# 5_dc_dc_3V3_EPS_Beacon.net
KiCad netlist of a schematic drawn in Altium Designer
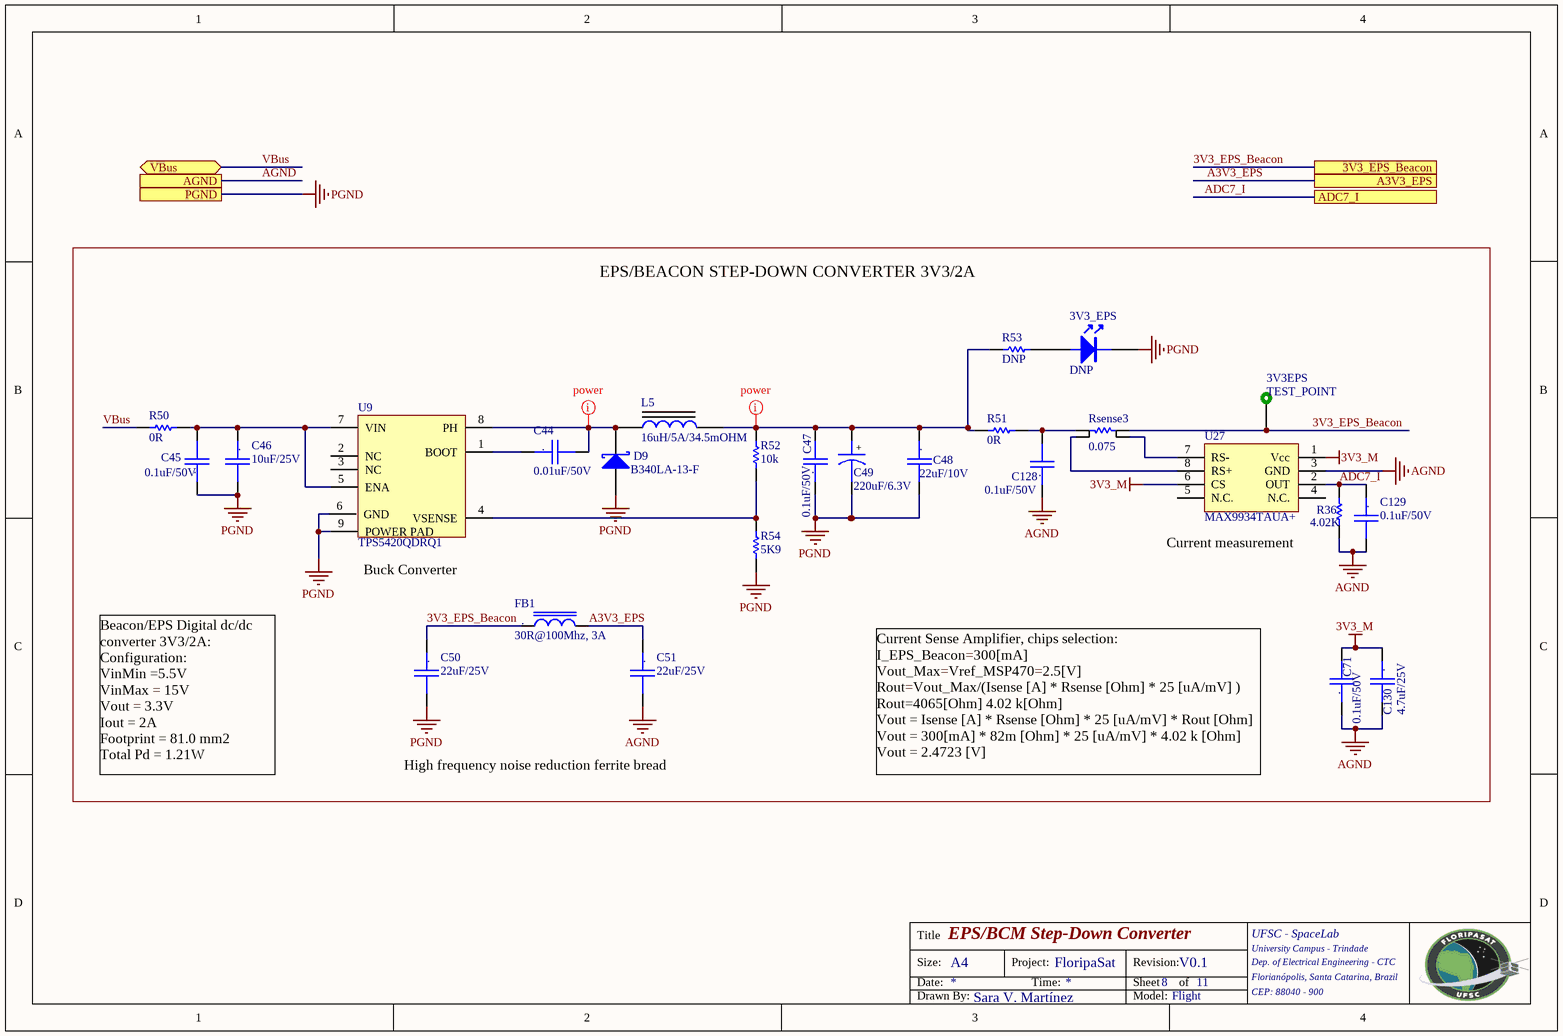
[diagram p0: 5_dc_dc_3V3_EPS_Beacon.SchDoc]

(export (version "E")
  (design (tool "Eeschema 10.0.6"))
  (components
    (comp (ref "3V3EPS")
      (value "TEST_POINT")
      (footprint "TEST_POINT")
      (description "Test point")
      (libsource (lib "Floripasat_lib") (part "TEST_POINT"))
    )
    (comp (ref "3V3_EPS")
      (value "DNP")
      (footprint "0603-LED")
      (description "SMD Green LED")
      (fields (field (name "PARTNUMBER") "150060VS75000"))
      (libsource (lib "FloripaSatSchlib") (part "LED/G_0603"))
    )
    (comp (ref "C44")
      (value "0.01uF/50V")
      (footprint "CC0805")
      (description "CAP CER 0.01uF 50V 10% X7R 0805")
      (fields (field (name "PARTNUMBER") "GRM216R71H103KA01D"))
      (libsource (lib "Floripasat_lib") (part "Cap_Cer_X7R_0.01uF_50V_0805"))
    )
    (comp (ref "C45")
      (value "0.1uF/50V")
      (footprint "CC0805")
      (description "CAP CER 0.1UF 50V 10% X7R 0805")
      (fields (field (name "PARTNUMBER") "GRM216R71H103KA01D"))
      (libsource (lib "FloripaSatSchlib") (part "Cap_Cer_X7R_0.1uF_25V_0805"))
    )
    (comp (ref "C46")
      (value "10uF/25V")
      (footprint "CC1206")
      (description "CAP CER 10uF 25V 10% X7R 1206")
      (fields (field (name "PARTNUMBER") "GRM31CR71E106KA12L"))
      (libsource (lib "Floripasat_lib") (part "Cap_Cer_X7R_10uF_25V_1206"))
    )
    (comp (ref "C47")
      (value "0.1uF/50V")
      (footprint "CC0805")
      (description "CAP CER 0.1UF 50V 10% X7R 0805")
      (fields (field (name "PARTNUMBER") "GRM216R71H103KA01D"))
      (libsource (lib "FloripaSatSchlib") (part "Cap_Cer_X7R_0.1uF_25V_0805"))
    )
    (comp (ref "C48")
      (value "22uF/10V")
      (footprint "CC1206")
      (description "CAP CER 22uF 10V 10% X7R 1206")
      (fields (field (name "PARTNUMBER") "GRM31CR71A226KE15L"))
      (libsource (lib "FloripaSatSchlib") (part "Cap_Cer_X7R_22uF_10V_1206"))
    )
    (comp (ref "C49")
      (value "220uF/6.3V")
      (footprint "FloripaSatPcbLib:cc1210")
      (description "CAP Tantalum 220uF 6.3V 20% 1210")
      (fields (field (name "PARTNUMBER") "6TPE220MAZB"))
      (libsource (lib "Floripasat_lib") (part "Cap_Tant_SMD_220uF_6.3V_1210"))
    )
    (comp (ref "C50")
      (value "22uF/25V")
      (footprint "CC1210")
      (description "CAP CER 22uF 25V 10% X7R 1210")
      (fields (field (name "PARTNUMBER") "GRM32ER71E226KE15L"))
      (libsource (lib "FloripaSatSchlib") (part "Cap_Cer_X7R_0.01uF_16V_1210"))
    )
    (comp (ref "C51")
      (value "22uF/25V")
      (footprint "CC1210")
      (description "CAP CER 22uF 25V 10% X7R 1210")
      (fields (field (name "PARTNUMBER") "GRM32ER71E226KE15L"))
      (libsource (lib "FloripaSatSchlib") (part "Cap_Cer_X7R_0.01uF_16V_1210"))
    )
    (comp (ref "C71")
      (value "0.1uF/50V")
      (footprint "CC0603")
      (description "CAP CER 0.1UF 50V 10% X7R 0603")
      (fields (field (name "PARTNUMBER") "GRM188R71H104KA93D"))
      (libsource (lib "FloripaSatSchlib") (part "Cap_Cer_X7R_0.1uF_50V_0603"))
    )
    (comp (ref "C128")
      (value "0.1uF/50V")
      (footprint "CC0603")
      (description "CAP CER 0.1UF 50V 10% X7R 0603")
      (fields (field (name "PARTNUMBER") "GRM188R71H104KA93D"))
      (libsource (lib "FloripaSatSchlib") (part "Cap_Cer_X7R_0.1uF_50V_0603"))
    )
    (comp (ref "C129")
      (value "0.1uF/50V")
      (footprint "CC0603")
      (description "CAP CER 0.1UF 50V 10% X7R 0603")
      (fields (field (name "PARTNUMBER") "GRM188R71H104KA93D"))
      (libsource (lib "FloripaSatSchlib") (part "Cap_Cer_X7R_0.1uF_50V_0603"))
    )
    (comp (ref "C130")
      (value "4.7uF/25V")
      (footprint "CC0805")
      (description "CAP CER 4.7uF 25V 10% X7R 0805")
      (fields (field (name "PARTNUMBER") "GRM21BR71E475KA73L"))
      (libsource (lib "FloripaSatSchlib") (part "Cap_Cer_X7R_4.7uF_25V_0805"))
    )
    (comp (ref "D9")
      (value "B340LA-13-F")
      (footprint "DO-214AC")
      (description "DIODE SCHOTTKY 40V 3A B340LA-13-F")
      (libsource (lib "FloripaSatSchlib") (part "DIODE_SCHOTTKY_40V_3A_B340LA-13-F"))
    )
    (comp (ref "FB1")
      (value "30R@100Mhz, 3A")
      (footprint "IND0805")
      (description "Ferrite Bead 30 OHM 3A 100MHz")
      (fields (field (name "PARTNUMBER") "BLM21PG300SN1D"))
      (libsource (lib "FloripaSatSchlib") (part "FB_30R_3A_100MHz_0805"))
    )
    (comp (ref "L5")
      (value "16uH/5A/34.5mOHM")
      (footprint "IND_744325xxx")
      (description "INDUCTOR 16UH 5A SMD")
      (fields (field (name "PARTNUMBER") "7443251600"))
      (libsource (lib "FloripaSatSchlib") (part "IND_POWER_16uH_5A_35.5mR"))
    )
    (comp (ref "R36")
      (value "4.02K")
      (footprint "0805")
      (description "RES 3k3 OHM 1/10W 0.1% 0805")
      (fields (field (name "PARTNUMBER") "CPF0805B3K3E1"))
      (libsource (lib "FloripaSatSchlib") (part "R3.3k_0.1%_1/10W_0805"))
    )
    (comp (ref "R50")
      (value "0R")
      (footprint "1206")
      (description "RES 0.0 OHM 1/2W JUMP 1206")
      (fields (field (name "PARTNUMBER") "CRCW12060000Z0EAHP"))
      (libsource (lib "FloripaSatSchlib") (part "R0R_JUMPER_1/2W_1206"))
    )
    (comp (ref "R51")
      (value "0R")
      (footprint "1206")
      (description "RES 0.0 OHM 1/2W JUMP 1206")
      (fields (field (name "PARTNUMBER") "CRCW12060000Z0EAHP"))
      (libsource (lib "FloripaSatSchlib") (part "R0R_JUMPER_1/2W_1206"))
    )
    (comp (ref "R52")
      (value "10k")
      (footprint "0805")
      (description "RES 10K OHM 1/8W 1%  0805")
      (fields (field (name "PARTNUMBER") "CRCW080510K0FKEA"))
      (libsource (lib "FloripaSatSchlib") (part "R10k_1%_1/8W_0805"))
    )
    (comp (ref "R53")
      (value "DNP")
      (footprint "0603")
      (description "RES 1.0K OHM 1/8W 1% 0603")
      (fields (field (name "PARTNUMBER") "MCT06030C1001FP500"))
      (libsource (lib "FloripaSatSchlib") (part "R1.0k_1%_1/8W_0603"))
    )
    (comp (ref "R54")
      (value "5K9")
      (footprint "0805")
      (description "RES 5K9 OHM 1/8W 1% 0805")
      (fields (field (name "PARTNUMBER") "71-CRCW0805-5.9K-E3"))
      (libsource (lib "FloripaSatSchlib") (part "R5.9K_1%_1/8W_0805"))
    )
    (comp (ref "Rsense3")
      (value "0.075")
      (footprint "1206 - ohmite")
      (description "Current Sense Resistors - SMD 0.05ohm .5% 4 Terminal")
      (fields (field (name "PARTNUMBER") "LVK12R050DER"))
      (libsource (lib "FloripaSatSchlib") (part "R0.05R_0.5%_0.5W_1206"))
    )
    (comp (ref "U9")
      (value "TPS5420QDRQ1")
      (footprint "SO8 Power PAD")
      (libsource (lib "FloripaSatSchlib") (part "TPS5420QDRQ1"))
    )
    (comp (ref "U27")
      (value "MAX9934TAUA+")
      (footprint "MSOP-8")
      (libsource (lib "componentes_6_11") (part "MAX9934TAUA+"))
    )
  )
  (nets
    (net (code "1") (name "/3V3_EPS_Beacon") (class "Default")
      (node (ref "3V3EPS") (pin "1") (pinfunction "1_1") (pintype "passive"))
      (node (ref "C50") (pin "1") (pinfunction "1_1") (pintype "passive"))
      (node (ref "FB1") (pin "1") (pinfunction "1_1") (pintype "passive"))
      (node (ref "Rsense3") (pin "2") (pinfunction "2_2") (pintype "passive"))
    )
    (net (code "2") (name "/A3V3_EPS") (class "Default")
      (node (ref "C51") (pin "1") (pinfunction "1_1") (pintype "passive"))
      (node (ref "FB1") (pin "2") (pinfunction "2_2") (pintype "passive"))
    )
    (net (code "3") (name "/ADC7_I") (class "Default")
      (node (ref "C129") (pin "1") (pinfunction "1_1") (pintype "passive"))
      (node (ref "R36") (pin "2") (pinfunction "2_2") (pintype "passive"))
      (node (ref "U27") (pin "2") (pinfunction "OUT_2") (pintype "passive"))
    )
    (net (code "4") (name "/VBus") (class "Default")
      (node (ref "R50") (pin "2") (pinfunction "2_2") (pintype "passive"))
    )
    (net (code "5") (name "3V3_M") (class "Default")
      (node (ref "C130") (pin "1") (pinfunction "1_1") (pintype "passive"))
      (node (ref "C71") (pin "2") (pinfunction "2_2") (pintype "passive"))
      (node (ref "U27") (pin "1") (pinfunction "Vcc_1") (pintype "passive"))
      (node (ref "U27") (pin "6") (pinfunction "CS_6") (pintype "passive"))
    )
    (net (code "6") (name "AGND") (class "Default")
      (node (ref "C128") (pin "1") (pinfunction "1_1") (pintype "passive"))
      (node (ref "C129") (pin "2") (pinfunction "2_2") (pintype "passive"))
      (node (ref "C130") (pin "2") (pinfunction "2_2") (pintype "passive"))
      (node (ref "C51") (pin "2") (pinfunction "2_2") (pintype "passive"))
      (node (ref "C71") (pin "1") (pinfunction "1_1") (pintype "passive"))
      (node (ref "R36") (pin "1") (pinfunction "1_1") (pintype "passive"))
      (node (ref "U27") (pin "3") (pinfunction "GND_3") (pintype "passive"))
    )
    (net (code "7") (name "Net-(3V3_EPS-A)") (class "Default")
      (node (ref "3V3_EPS") (pin "1") (pinfunction "A_1") (pintype "passive"))
      (node (ref "R53") (pin "1") (pinfunction "1_1") (pintype "passive"))
    )
    (net (code "8") (name "Net-(C47-Pad2)") (class "Default")
      (node (ref "C47") (pin "2") (pinfunction "2_2") (pintype "passive"))
      (node (ref "C48") (pin "1") (pinfunction "1_1") (pintype "passive"))
      (node (ref "C49") (pin "1") (pinfunction "1_1") (pintype "passive"))
      (node (ref "L5") (pin "2") (pinfunction "2_2") (pintype "passive"))
      (node (ref "R51") (pin "2") (pinfunction "2_2") (pintype "passive"))
      (node (ref "R52") (pin "2") (pinfunction "2_2") (pintype "passive"))
      (node (ref "R53") (pin "2") (pinfunction "2_2") (pintype "passive"))
    )
    (net (code "9") (name "Net-(C128-Pad2)") (class "Default")
      (node (ref "C128") (pin "2") (pinfunction "2_2") (pintype "passive"))
      (node (ref "R51") (pin "1") (pinfunction "1_1") (pintype "passive"))
      (node (ref "Rsense3") (pin "1") (pinfunction "1_1") (pintype "passive"))
    )
    (net (code "10") (name "Net-(D9-K)") (class "Default")
      (node (ref "C44") (pin "2") (pinfunction "2_2") (pintype "passive"))
      (node (ref "D9") (pin "1") (pinfunction "K_1") (pintype "passive"))
      (node (ref "L5") (pin "1") (pinfunction "1_1") (pintype "passive"))
      (node (ref "U9") (pin "8") (pinfunction "PH_8") (pintype "passive"))
    )
    (net (code "11") (name "Net-(U9-BOOT)") (class "Default")
      (node (ref "C44") (pin "1") (pinfunction "1_1") (pintype "passive"))
      (node (ref "U9") (pin "1") (pinfunction "BOOT_1") (pintype "passive"))
    )
    (net (code "12") (name "Net-(U9-ENA)") (class "Default")
      (node (ref "C45") (pin "2") (pinfunction "2_2") (pintype "passive"))
      (node (ref "C46") (pin "1") (pinfunction "1_1") (pintype "passive"))
      (node (ref "R50") (pin "1") (pinfunction "1_1") (pintype "passive"))
      (node (ref "U9") (pin "5") (pinfunction "ENA_5") (pintype "passive"))
      (node (ref "U9") (pin "7") (pinfunction "VIN_7") (pintype "passive"))
    )
    (net (code "13") (name "Net-(U9-VSENSE)") (class "Default")
      (node (ref "R52") (pin "1") (pinfunction "1_1") (pintype "passive"))
      (node (ref "R54") (pin "2") (pinfunction "2_2") (pintype "passive"))
      (node (ref "U9") (pin "4") (pinfunction "VSENSE_4") (pintype "passive"))
    )
    (net (code "14") (name "Net-(U27-RS+)") (class "Default")
      (node (ref "Rsense3") (pin "3") (pinfunction "3_3") (pintype "passive"))
      (node (ref "U27") (pin "8") (pinfunction "RS+_8") (pintype "passive"))
    )
    (net (code "15") (name "Net-(U27-RS-)") (class "Default")
      (node (ref "Rsense3") (pin "4") (pinfunction "4_4") (pintype "passive"))
      (node (ref "U27") (pin "7") (pinfunction "RS-_7") (pintype "passive"))
    )
    (net (code "16") (name "PGND") (class "Default")
      (node (ref "3V3_EPS") (pin "2") (pinfunction "K_2") (pintype "passive"))
      (node (ref "C45") (pin "1") (pinfunction "1_1") (pintype "passive"))
      (node (ref "C46") (pin "2") (pinfunction "2_2") (pintype "passive"))
      (node (ref "C47") (pin "1") (pinfunction "1_1") (pintype "passive"))
      (node (ref "C48") (pin "2") (pinfunction "2_2") (pintype "passive"))
      (node (ref "C49") (pin "2") (pinfunction "2_2") (pintype "passive"))
      (node (ref "C50") (pin "2") (pinfunction "2_2") (pintype "passive"))
      (node (ref "D9") (pin "2") (pinfunction "A_2") (pintype "passive"))
      (node (ref "R54") (pin "1") (pinfunction "1_1") (pintype "passive"))
      (node (ref "U9") (pin "6") (pinfunction "GND_6") (pintype "passive"))
      (node (ref "U9") (pin "9") (pinfunction "POWER_PAD_9") (pintype "passive"))
    )
    (net (code "17") (name "unconnected-(U9-NC-Pad2)") (class "Default")
      (node (ref "U9") (pin "2") (pinfunction "NC_2") (pintype "passive"))
    )
    (net (code "18") (name "unconnected-(U9-NC-Pad3)") (class "Default")
      (node (ref "U9") (pin "3") (pinfunction "NC_3") (pintype "passive"))
    )
    (net (code "19") (name "unconnected-(U27-N.C.-Pad4)") (class "Default")
      (node (ref "U27") (pin "4") (pinfunction "N.C._4") (pintype "passive"))
    )
    (net (code "20") (name "unconnected-(U27-N.C.-Pad5)") (class "Default")
      (node (ref "U27") (pin "5") (pinfunction "N.C._5") (pintype "passive"))
    )
  )
)
